# nocLock_Rev1.net
KiCad netlist of a schematic drawn in EAGLE
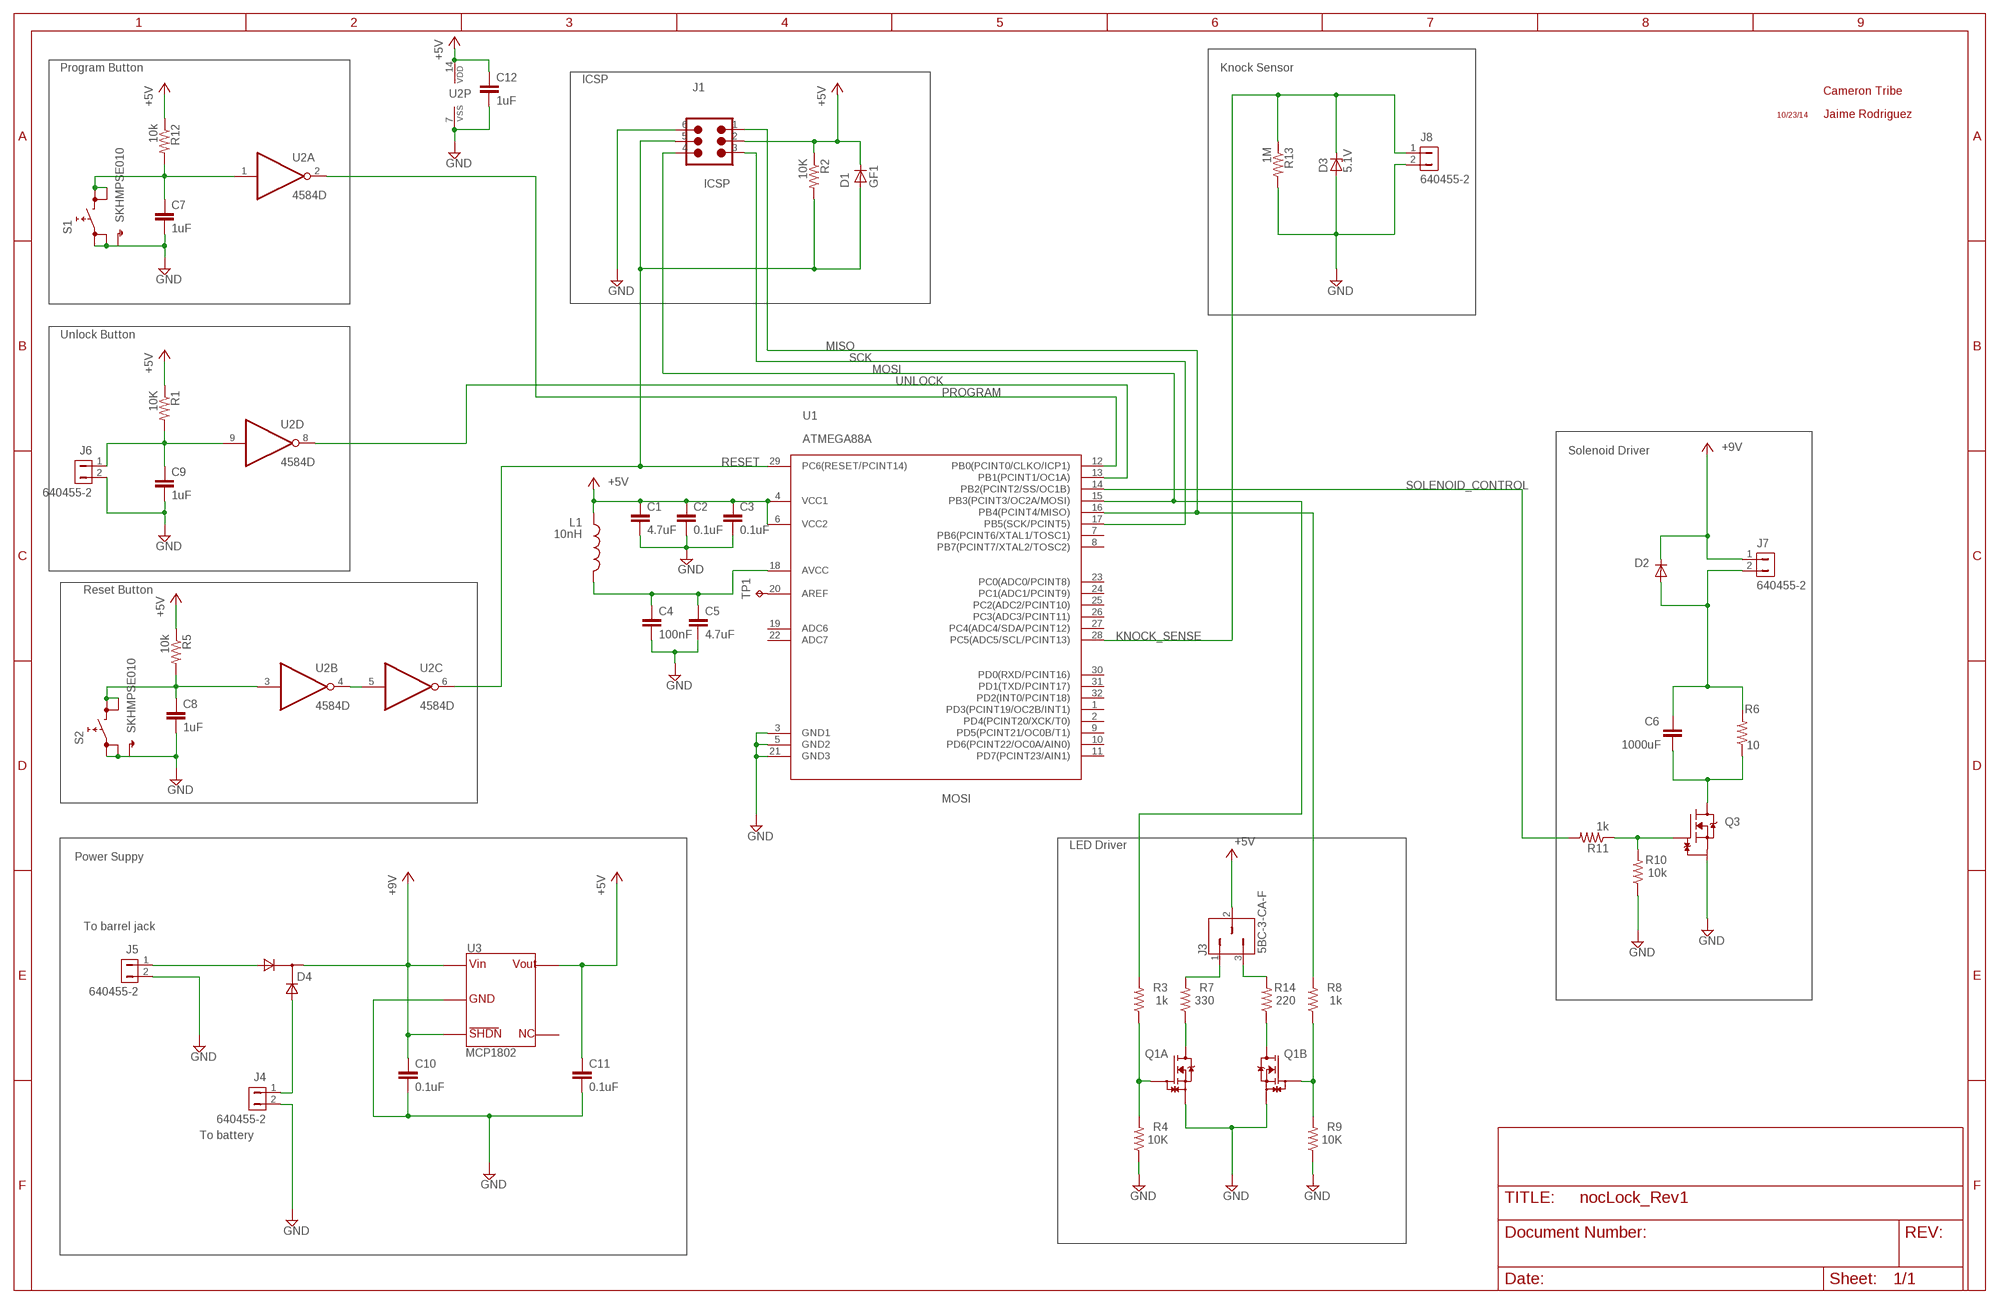
[diagram p0: schematic, sheet 1]

(export (version "E")
  (design (tool "Eeschema 10.0.6"))
  (components
    (comp (ref "C1")
      (value "4.7uF")
      (footprint "eagle-import:C0805")
      (libsource (lib "eagle-import") (part "C-EUC0805"))
    )
    (comp (ref "C2")
      (value "0.1uF")
      (footprint "eagle-import:C0805")
      (libsource (lib "eagle-import") (part "C-EUC0805"))
    )
    (comp (ref "C3")
      (value "0.1uF")
      (footprint "eagle-import:C0805")
      (libsource (lib "eagle-import") (part "C-EUC0805"))
    )
    (comp (ref "C4")
      (value "100nF")
      (footprint "eagle-import:C0805")
      (libsource (lib "eagle-import") (part "C-EUC0805"))
    )
    (comp (ref "C5")
      (value "4.7uF")
      (footprint "eagle-import:C0805")
      (libsource (lib "eagle-import") (part "C-EUC0805"))
    )
    (comp (ref "C6")
      (value "1000uF")
      (footprint "eagle-import:C0805")
      (libsource (lib "eagle-import") (part "C-EUC0805"))
    )
    (comp (ref "C7")
      (value "1uF")
      (footprint "eagle-import:C0805")
      (libsource (lib "eagle-import") (part "C-EUC0805"))
    )
    (comp (ref "C8")
      (value "1uF")
      (footprint "eagle-import:C0805")
      (libsource (lib "eagle-import") (part "C-EUC0805"))
    )
    (comp (ref "C9")
      (value "1uF")
      (footprint "eagle-import:C0805")
      (libsource (lib "eagle-import") (part "C-EUC0805"))
    )
    (comp (ref "C10")
      (value "0.1uF")
      (footprint "eagle-import:C0805")
      (libsource (lib "eagle-import") (part "C-EUC0805"))
    )
    (comp (ref "C11")
      (value "0.1uF")
      (footprint "eagle-import:C0805")
      (libsource (lib "eagle-import") (part "C-EUC0805"))
    )
    (comp (ref "C12")
      (value "1uF")
      (footprint "eagle-import:C0805")
      (libsource (lib "eagle-import") (part "C-EUC0805"))
    )
    (comp (ref "D1")
      (value "GF1")
      (footprint "eagle-import:SMA-DO214AC")
      (libsource (lib "eagle-import") (part "GF1"))
    )
    (comp (ref "D2")
      (value "GF1")
      (footprint "eagle-import:SMA-DO214AC")
      (libsource (lib "eagle-import") (part "GF1"))
    )
    (comp (ref "D3")
      (value "5.1V")
      (footprint "eagle-import:SOT23")
      (libsource (lib "eagle-import") (part "ZENER-DIODESOT23"))
    )
    (comp (ref "D4")
      (value "PMEG2005CT,215")
      (footprint "eagle-import:SOT-23")
      (libsource (lib "eagle-import") (part "PMEG2005CT,215"))
    )
    (comp (ref "J1")
      (value "ICSP")
      (footprint "eagle-import:ICSP")
      (libsource (lib "eagle-import") (part "ICSP"))
    )
    (comp (ref "J3")
      (value "5BC-3-CA-F")
      (footprint "eagle-import:3_PIN_CONNECTOR")
      (libsource (lib "eagle-import") (part "5BC-3-CA-F"))
    )
    (comp (ref "J4")
      (value "640455-2")
      (footprint "eagle-import:2-PIN_CONNECTOR")
      (libsource (lib "eagle-import") (part "640455-2"))
    )
    (comp (ref "J5")
      (value "640455-2")
      (footprint "eagle-import:2-PIN_CONNECTOR")
      (libsource (lib "eagle-import") (part "640455-2"))
    )
    (comp (ref "J6")
      (value "640455-2")
      (footprint "eagle-import:2-PIN_CONNECTOR")
      (libsource (lib "eagle-import") (part "640455-2"))
    )
    (comp (ref "J7")
      (value "640455-2")
      (footprint "eagle-import:2-PIN_CONNECTOR")
      (libsource (lib "eagle-import") (part "640455-2"))
    )
    (comp (ref "J8")
      (value "640455-2")
      (footprint "eagle-import:2-PIN_CONNECTOR")
      (libsource (lib "eagle-import") (part "640455-2"))
    )
    (comp (ref "L1")
      (value "10nH")
      (footprint "eagle-import:L4532M")
      (libsource (lib "eagle-import") (part "L-USL4532C"))
    )
    (comp (ref "Q1")
      (value "DMN63D8LDW-7")
      (footprint "eagle-import:SOT363")
      (libsource (lib "eagle-import") (part "DMN63D8LDW-7"))
    )
    (comp (ref "Q3")
      (value "DMG1012UW-7")
      (footprint "eagle-import:SOT323")
      (libsource (lib "eagle-import") (part "DMG1012UW-7"))
    )
    (comp (ref "R1")
      (value "10K")
      (footprint "eagle-import:R0805")
      (libsource (lib "eagle-import") (part "R-US_R0805"))
    )
    (comp (ref "R2")
      (value "10K")
      (footprint "eagle-import:R0805")
      (libsource (lib "eagle-import") (part "R-US_R0805"))
    )
    (comp (ref "R3")
      (value "1k")
      (footprint "eagle-import:R0805")
      (libsource (lib "eagle-import") (part "R-US_R0805"))
    )
    (comp (ref "R4")
      (value "10K")
      (footprint "eagle-import:R0805")
      (libsource (lib "eagle-import") (part "R-US_R0805"))
    )
    (comp (ref "R5")
      (value "10k")
      (footprint "eagle-import:R0805")
      (libsource (lib "eagle-import") (part "R-US_R0805"))
    )
    (comp (ref "R6")
      (value "10")
      (footprint "eagle-import:R2512")
      (libsource (lib "eagle-import") (part "R-US_R2512"))
    )
    (comp (ref "R7")
      (value "330")
      (footprint "eagle-import:R0805")
      (libsource (lib "eagle-import") (part "R-US_R0805"))
    )
    (comp (ref "R8")
      (value "1k")
      (footprint "eagle-import:R0805")
      (libsource (lib "eagle-import") (part "R-US_R0805"))
    )
    (comp (ref "R9")
      (value "10K")
      (footprint "eagle-import:R0805")
      (libsource (lib "eagle-import") (part "R-US_R0805"))
    )
    (comp (ref "R10")
      (value "10k")
      (footprint "eagle-import:R0805")
      (libsource (lib "eagle-import") (part "R-US_R0805"))
    )
    (comp (ref "R11")
      (value "1k")
      (footprint "eagle-import:R0805")
      (libsource (lib "eagle-import") (part "R-US_R0805"))
    )
    (comp (ref "R12")
      (value "10k")
      (footprint "eagle-import:R0805")
      (libsource (lib "eagle-import") (part "R-US_R0805"))
    )
    (comp (ref "R13")
      (value "1M")
      (footprint "eagle-import:R0805")
      (libsource (lib "eagle-import") (part "R-US_R0805"))
    )
    (comp (ref "R14")
      (value "220")
      (footprint "eagle-import:R0805")
      (libsource (lib "eagle-import") (part "R-US_R0805"))
    )
    (comp (ref "S1")
      (value "SKHMPSE010")
      (footprint "eagle-import:SKHMPXE010")
      (libsource (lib "eagle-import") (part "SKHMPE010S"))
    )
    (comp (ref "S2")
      (value "SKHMPSE010")
      (footprint "eagle-import:SKHMPXE010")
      (libsource (lib "eagle-import") (part "SKHMPE010S"))
    )
    (comp (ref "TP1")
      (value "TPTP19R")
      (footprint "eagle-import:TP19R")
      (libsource (lib "eagle-import") (part "TPTP19R"))
    )
    (comp (ref "U1")
      (value "ATMEGA88A")
      (footprint "eagle-import:TQFP32")
      (libsource (lib "eagle-import") (part "ATMEGA88A"))
    )
    (comp (ref "U2")
      (value "4584D")
      (footprint "eagle-import:SO14")
      (libsource (lib "eagle-import") (part "4584D"))
    )
    (comp (ref "U3")
      (value "MCP1802")
      (footprint "eagle-import:SOT23-5")
      (libsource (lib "eagle-import") (part "MCP1802"))
    )
  )
  (nets
    (net (code "1") (name "+5V") (class "Default")
      (node (ref "C1") (pin "1") (pinfunction "1_1") (pintype "passive"))
      (node (ref "C11") (pin "1") (pinfunction "1_1") (pintype "passive"))
      (node (ref "C12") (pin "1") (pinfunction "1_1") (pintype "passive"))
      (node (ref "C2") (pin "1") (pinfunction "1_1") (pintype "passive"))
      (node (ref "C3") (pin "1") (pinfunction "1_1") (pintype "passive"))
      (node (ref "D1") (pin "K") (pinfunction "C_K") (pintype "passive"))
      (node (ref "J1") (pin "2") (pinfunction "2_2") (pintype "passive"))
      (node (ref "J3") (pin "2") (pinfunction "2_2") (pintype "passive"))
      (node (ref "L1") (pin "1") (pinfunction "1_1") (pintype "passive"))
      (node (ref "R1") (pin "1") (pinfunction "1_1") (pintype "passive"))
      (node (ref "R12") (pin "1") (pinfunction "1_1") (pintype "passive"))
      (node (ref "R2") (pin "1") (pinfunction "1_1") (pintype "passive"))
      (node (ref "R5") (pin "1") (pinfunction "1_1") (pintype "passive"))
      (node (ref "U1") (pin "4") (pinfunction "VCC1_4") (pintype "power_in"))
      (node (ref "U1") (pin "6") (pinfunction "VCC2_6") (pintype "passive"))
      (node (ref "U2") (pin "14") (pinfunction "VDD_14") (pintype "power_in"))
      (node (ref "U3") (pin "5") (pinfunction "VOUT_5") (pintype "passive"))
    )
    (net (code "2") (name "+9V") (class "Default")
      (node (ref "C10") (pin "1") (pinfunction "1_1") (pintype "passive"))
      (node (ref "D2") (pin "K") (pinfunction "C_K") (pintype "passive"))
      (node (ref "D4") (pin "2") (pinfunction "C_2") (pintype "passive"))
      (node (ref "J7") (pin "1") (pinfunction "1_1") (pintype "passive"))
      (node (ref "U3") (pin "1") (pinfunction "VIN_1") (pintype "passive"))
      (node (ref "U3") (pin "3") (pinfunction "SHDN_3") (pintype "passive"))
    )
    (net (code "3") (name "/KNOCK_SENSE") (class "Default")
      (node (ref "D3") (pin "3") (pinfunction "C_3") (pintype "passive"))
      (node (ref "J8") (pin "1") (pinfunction "1_1") (pintype "passive"))
      (node (ref "R13") (pin "1") (pinfunction "1_1") (pintype "passive"))
      (node (ref "U1") (pin "28") (pinfunction "PC5(ADC5/SCL/PCINT13)_28") (pintype "bidirectional"))
    )
    (net (code "4") (name "/MISO") (class "Default")
      (node (ref "J1") (pin "1") (pinfunction "1_1") (pintype "passive"))
      (node (ref "R8") (pin "2") (pinfunction "2_2") (pintype "passive"))
      (node (ref "U1") (pin "16") (pinfunction "PB4(PCINT4/MISO)_16") (pintype "bidirectional"))
    )
    (net (code "5") (name "/MOSI") (class "Default")
      (node (ref "J1") (pin "4") (pinfunction "4_4") (pintype "passive"))
      (node (ref "R3") (pin "2") (pinfunction "2_2") (pintype "passive"))
      (node (ref "U1") (pin "15") (pinfunction "PB3(PCINT3/OC2A/MOSI)_15") (pintype "bidirectional"))
    )
    (net (code "6") (name "/PROGRAM") (class "Default")
      (node (ref "U1") (pin "12") (pinfunction "PB0(PCINT0/CLKO/ICP1)_12") (pintype "bidirectional"))
      (node (ref "U2") (pin "2") (pinfunction "O_2") (pintype "output"))
    )
    (net (code "7") (name "/RESET") (class "Default")
      (node (ref "D1") (pin "A") (pinfunction "A_A") (pintype "passive"))
      (node (ref "J1") (pin "5") (pinfunction "5_5") (pintype "passive"))
      (node (ref "R2") (pin "2") (pinfunction "2_2") (pintype "passive"))
      (node (ref "U1") (pin "29") (pinfunction "PC6(RESET/PCINT14)_29") (pintype "bidirectional"))
      (node (ref "U2") (pin "6") (pinfunction "O_6") (pintype "output"))
    )
    (net (code "8") (name "/SCK") (class "Default")
      (node (ref "J1") (pin "3") (pinfunction "3_3") (pintype "passive"))
      (node (ref "U1") (pin "17") (pinfunction "PB5(SCK/PCINT5)_17") (pintype "bidirectional"))
    )
    (net (code "9") (name "/SOLENOID_CONTROL") (class "Default")
      (node (ref "R11") (pin "2") (pinfunction "2_2") (pintype "passive"))
      (node (ref "U1") (pin "14") (pinfunction "PB2(PCINT2/SS/OC1B)_14") (pintype "bidirectional"))
    )
    (net (code "10") (name "/UNLOCK") (class "Default")
      (node (ref "U1") (pin "13") (pinfunction "PB1(PCINT1/OC1A)_13") (pintype "bidirectional"))
      (node (ref "U2") (pin "8") (pinfunction "O_8") (pintype "output"))
    )
    (net (code "11") (name "GND") (class "Default")
      (node (ref "C1") (pin "2") (pinfunction "2_2") (pintype "passive"))
      (node (ref "C10") (pin "2") (pinfunction "2_2") (pintype "passive"))
      (node (ref "C11") (pin "2") (pinfunction "2_2") (pintype "passive"))
      (node (ref "C12") (pin "2") (pinfunction "2_2") (pintype "passive"))
      (node (ref "C2") (pin "2") (pinfunction "2_2") (pintype "passive"))
      (node (ref "C3") (pin "2") (pinfunction "2_2") (pintype "passive"))
      (node (ref "C4") (pin "2") (pinfunction "2_2") (pintype "passive"))
      (node (ref "C5") (pin "2") (pinfunction "2_2") (pintype "passive"))
      (node (ref "C7") (pin "2") (pinfunction "2_2") (pintype "passive"))
      (node (ref "C8") (pin "2") (pinfunction "2_2") (pintype "passive"))
      (node (ref "C9") (pin "2") (pinfunction "2_2") (pintype "passive"))
      (node (ref "D3") (pin "1") (pinfunction "A_1") (pintype "passive"))
      (node (ref "J1") (pin "6") (pinfunction "6_6") (pintype "passive"))
      (node (ref "J4") (pin "2") (pinfunction "2_2") (pintype "passive"))
      (node (ref "J5") (pin "2") (pinfunction "2_2") (pintype "passive"))
      (node (ref "J6") (pin "2") (pinfunction "2_2") (pintype "passive"))
      (node (ref "J8") (pin "2") (pinfunction "2_2") (pintype "passive"))
      (node (ref "Q1") (pin "S1") (pinfunction "S_S1") (pintype "passive"))
      (node (ref "Q1") (pin "S2") (pinfunction "S_S2") (pintype "passive"))
      (node (ref "Q3") (pin "3") (pinfunction "S_3") (pintype "passive"))
      (node (ref "R10") (pin "1") (pinfunction "1_1") (pintype "passive"))
      (node (ref "R13") (pin "2") (pinfunction "2_2") (pintype "passive"))
      (node (ref "R4") (pin "1") (pinfunction "1_1") (pintype "passive"))
      (node (ref "R9") (pin "1") (pinfunction "1_1") (pintype "passive"))
      (node (ref "S1") (pin "1") (pinfunction "1.1_1") (pintype "passive"))
      (node (ref "S1") (pin "2") (pinfunction "1.2_2") (pintype "passive"))
      (node (ref "S2") (pin "1") (pinfunction "1.1_1") (pintype "passive"))
      (node (ref "S2") (pin "2") (pinfunction "1.2_2") (pintype "passive"))
      (node (ref "U1") (pin "21") (pinfunction "GND3_21") (pintype "power_in"))
      (node (ref "U1") (pin "3") (pinfunction "GND1_3") (pintype "power_in"))
      (node (ref "U1") (pin "5") (pinfunction "GND2_5") (pintype "power_in"))
      (node (ref "U2") (pin "7") (pinfunction "VSS_7") (pintype "power_in"))
      (node (ref "U3") (pin "2") (pinfunction "GND_2") (pintype "power_in"))
    )
    (net (code "12") (name "Net-(C6-Pad1)") (class "Default")
      (node (ref "C6") (pin "1") (pinfunction "1_1") (pintype "passive"))
      (node (ref "D2") (pin "A") (pinfunction "A_A") (pintype "passive"))
      (node (ref "J7") (pin "2") (pinfunction "2_2") (pintype "passive"))
      (node (ref "R6") (pin "2") (pinfunction "2_2") (pintype "passive"))
    )
    (net (code "13") (name "Net-(D4-A1)") (class "Default")
      (node (ref "D4") (pin "3") (pinfunction "A1_3") (pintype "passive"))
      (node (ref "J5") (pin "1") (pinfunction "1_1") (pintype "passive"))
    )
    (net (code "14") (name "Net-(D4-A2)") (class "Default")
      (node (ref "D4") (pin "1") (pinfunction "A2_1") (pintype "passive"))
      (node (ref "J4") (pin "1") (pinfunction "1_1") (pintype "passive"))
    )
    (net (code "15") (name "Net-(J3-Pad1)") (class "Default")
      (node (ref "J3") (pin "1") (pinfunction "1_1") (pintype "passive"))
      (node (ref "R7") (pin "2") (pinfunction "2_2") (pintype "passive"))
    )
    (net (code "16") (name "Net-(J3-Pad3)") (class "Default")
      (node (ref "J3") (pin "3") (pinfunction "3_3") (pintype "passive"))
      (node (ref "R14") (pin "2") (pinfunction "2_2") (pintype "passive"))
    )
    (net (code "17") (name "Net-(Q1A-D)") (class "Default")
      (node (ref "Q1") (pin "D1") (pinfunction "D_D1") (pintype "passive"))
      (node (ref "R7") (pin "1") (pinfunction "1_1") (pintype "passive"))
    )
    (net (code "18") (name "Net-(Q1A-G)") (class "Default")
      (node (ref "Q1") (pin "G1") (pinfunction "G_G1") (pintype "passive"))
      (node (ref "R3") (pin "1") (pinfunction "1_1") (pintype "passive"))
      (node (ref "R4") (pin "2") (pinfunction "2_2") (pintype "passive"))
    )
    (net (code "19") (name "Net-(Q1B-D)") (class "Default")
      (node (ref "Q1") (pin "D2") (pinfunction "D_D2") (pintype "passive"))
      (node (ref "R14") (pin "1") (pinfunction "1_1") (pintype "passive"))
    )
    (net (code "20") (name "Net-(Q1B-G)") (class "Default")
      (node (ref "Q1") (pin "G2") (pinfunction "G_G2") (pintype "passive"))
      (node (ref "R8") (pin "1") (pinfunction "1_1") (pintype "passive"))
      (node (ref "R9") (pin "2") (pinfunction "2_2") (pintype "passive"))
    )
    (net (code "21") (name "Net-(Q3-D)") (class "Default")
      (node (ref "C6") (pin "2") (pinfunction "2_2") (pintype "passive"))
      (node (ref "Q3") (pin "1") (pinfunction "D_1") (pintype "passive"))
      (node (ref "R6") (pin "1") (pinfunction "1_1") (pintype "passive"))
    )
    (net (code "22") (name "Net-(Q3-G)") (class "Default")
      (node (ref "Q3") (pin "2") (pinfunction "G_2") (pintype "passive"))
      (node (ref "R10") (pin "2") (pinfunction "2_2") (pintype "passive"))
      (node (ref "R11") (pin "1") (pinfunction "1_1") (pintype "passive"))
    )
    (net (code "23") (name "Net-(S1-2.1)") (class "Default")
      (node (ref "C7") (pin "1") (pinfunction "1_1") (pintype "passive"))
      (node (ref "R12") (pin "2") (pinfunction "2_2") (pintype "passive"))
      (node (ref "S1") (pin "3") (pinfunction "2.1_3") (pintype "passive"))
      (node (ref "S1") (pin "4") (pinfunction "2.2_4") (pintype "passive"))
      (node (ref "U2") (pin "1") (pinfunction "I_1") (pintype "input"))
    )
    (net (code "24") (name "Net-(S2-2.1)") (class "Default")
      (node (ref "C8") (pin "1") (pinfunction "1_1") (pintype "passive"))
      (node (ref "R5") (pin "2") (pinfunction "2_2") (pintype "passive"))
      (node (ref "S2") (pin "3") (pinfunction "2.1_3") (pintype "passive"))
      (node (ref "S2") (pin "4") (pinfunction "2.2_4") (pintype "passive"))
      (node (ref "U2") (pin "3") (pinfunction "I_3") (pintype "input"))
    )
    (net (code "25") (name "Net-(U1-AREF)") (class "Default")
      (node (ref "TP1") (pin "TP") (pinfunction "TP_TP") (pintype "input"))
      (node (ref "U1") (pin "20") (pinfunction "AREF_20") (pintype "power_in"))
    )
    (net (code "26") (name "Net-(U1-AVCC)") (class "Default")
      (node (ref "C4") (pin "1") (pinfunction "1_1") (pintype "passive"))
      (node (ref "C5") (pin "1") (pinfunction "1_1") (pintype "passive"))
      (node (ref "L1") (pin "2") (pinfunction "2_2") (pintype "passive"))
      (node (ref "U1") (pin "18") (pinfunction "AVCC_18") (pintype "power_in"))
    )
    (net (code "27") (name "Net-(U2B-O)") (class "Default")
      (node (ref "U2") (pin "4") (pinfunction "O_4") (pintype "output"))
      (node (ref "U2") (pin "5") (pinfunction "I_5") (pintype "input"))
    )
    (net (code "28") (name "Net-(U2D-I)") (class "Default")
      (node (ref "C9") (pin "1") (pinfunction "1_1") (pintype "passive"))
      (node (ref "J6") (pin "1") (pinfunction "1_1") (pintype "passive"))
      (node (ref "R1") (pin "2") (pinfunction "2_2") (pintype "passive"))
      (node (ref "U2") (pin "9") (pinfunction "I_9") (pintype "input"))
    )
    (net (code "29") (name "unconnected-(S1-SH-Pad5)") (class "Default")
      (node (ref "S1") (pin "5") (pinfunction "SH_5") (pintype "passive"))
    )
    (net (code "30") (name "unconnected-(S2-SH-Pad5)") (class "Default")
      (node (ref "S2") (pin "5") (pinfunction "SH_5") (pintype "passive"))
    )
    (net (code "31") (name "unconnected-(U1-ADC6-Pad19)") (class "Default")
      (node (ref "U1") (pin "19") (pinfunction "ADC6_19") (pintype "bidirectional"))
    )
    (net (code "32") (name "unconnected-(U1-ADC7-Pad22)") (class "Default")
      (node (ref "U1") (pin "22") (pinfunction "ADC7_22") (pintype "bidirectional"))
    )
    (net (code "33") (name "unconnected-(U1-PB6(PCINT6{slash}XTAL1{slash}TOSC1)-Pad7)") (class "Default")
      (node (ref "U1") (pin "7") (pinfunction "PB6(PCINT6/XTAL1/TOSC1)_7") (pintype "bidirectional"))
    )
    (net (code "34") (name "unconnected-(U1-PB7(PCINT7{slash}XTAL2{slash}TOSC2)-Pad8)") (class "Default")
      (node (ref "U1") (pin "8") (pinfunction "PB7(PCINT7/XTAL2/TOSC2)_8") (pintype "bidirectional"))
    )
    (net (code "35") (name "unconnected-(U1-PC0(ADC0{slash}PCINT8)-Pad23)") (class "Default")
      (node (ref "U1") (pin "23") (pinfunction "PC0(ADC0/PCINT8)_23") (pintype "bidirectional"))
    )
    (net (code "36") (name "unconnected-(U1-PC1(ADC1{slash}PCINT9)-Pad24)") (class "Default")
      (node (ref "U1") (pin "24") (pinfunction "PC1(ADC1/PCINT9)_24") (pintype "bidirectional"))
    )
    (net (code "37") (name "unconnected-(U1-PC2(ADC2{slash}PCINT10)-Pad25)") (class "Default")
      (node (ref "U1") (pin "25") (pinfunction "PC2(ADC2/PCINT10)_25") (pintype "bidirectional"))
    )
    (net (code "38") (name "unconnected-(U1-PC3(ADC3{slash}PCINT11)-Pad26)") (class "Default")
      (node (ref "U1") (pin "26") (pinfunction "PC3(ADC3/PCINT11)_26") (pintype "bidirectional"))
    )
    (net (code "39") (name "unconnected-(U1-PC4(ADC4{slash}SDA{slash}PCINT12)-Pad27)") (class "Default")
      (node (ref "U1") (pin "27") (pinfunction "PC4(ADC4/SDA/PCINT12)_27") (pintype "bidirectional"))
    )
    (net (code "40") (name "unconnected-(U1-PD0(RXD{slash}PCINT16)-Pad30)") (class "Default")
      (node (ref "U1") (pin "30") (pinfunction "PD0(RXD/PCINT16)_30") (pintype "bidirectional"))
    )
    (net (code "41") (name "unconnected-(U1-PD1(TXD{slash}PCINT17)-Pad31)") (class "Default")
      (node (ref "U1") (pin "31") (pinfunction "PD1(TXD/PCINT17)_31") (pintype "bidirectional"))
    )
    (net (code "42") (name "unconnected-(U1-PD2(INT0{slash}PCINT18)-Pad32)") (class "Default")
      (node (ref "U1") (pin "32") (pinfunction "PD2(INT0/PCINT18)_32") (pintype "bidirectional"))
    )
    (net (code "43") (name "unconnected-(U1-PD3(PCINT19{slash}OC2B{slash}INT1)-Pad1)") (class "Default")
      (node (ref "U1") (pin "1") (pinfunction "PD3(PCINT19/OC2B/INT1)_1") (pintype "bidirectional"))
    )
    (net (code "44") (name "unconnected-(U1-PD4(PCINT20{slash}XCK{slash}T0)-Pad2)") (class "Default")
      (node (ref "U1") (pin "2") (pinfunction "PD4(PCINT20/XCK/T0)_2") (pintype "bidirectional"))
    )
    (net (code "45") (name "unconnected-(U1-PD5(PCINT21{slash}OC0B{slash}T1)-Pad9)") (class "Default")
      (node (ref "U1") (pin "9") (pinfunction "PD5(PCINT21/OC0B/T1)_9") (pintype "bidirectional"))
    )
    (net (code "46") (name "unconnected-(U1-PD6(PCINT22{slash}OC0A{slash}AIN0)-Pad10)") (class "Default")
      (node (ref "U1") (pin "10") (pinfunction "PD6(PCINT22/OC0A/AIN0)_10") (pintype "bidirectional"))
    )
    (net (code "47") (name "unconnected-(U1-PD7(PCINT23{slash}AIN1)-Pad11)") (class "Default")
      (node (ref "U1") (pin "11") (pinfunction "PD7(PCINT23/AIN1)_11") (pintype "bidirectional"))
    )
    (net (code "48") (name "unconnected-(U3-NC-Pad4)") (class "Default")
      (node (ref "U3") (pin "4") (pinfunction "NC_4") (pintype "no_connect"))
    )
  )
)
